# SCH_Dise_o2_2023-11-16.net
KiCad netlist of a schematic drawn in EasyEDA
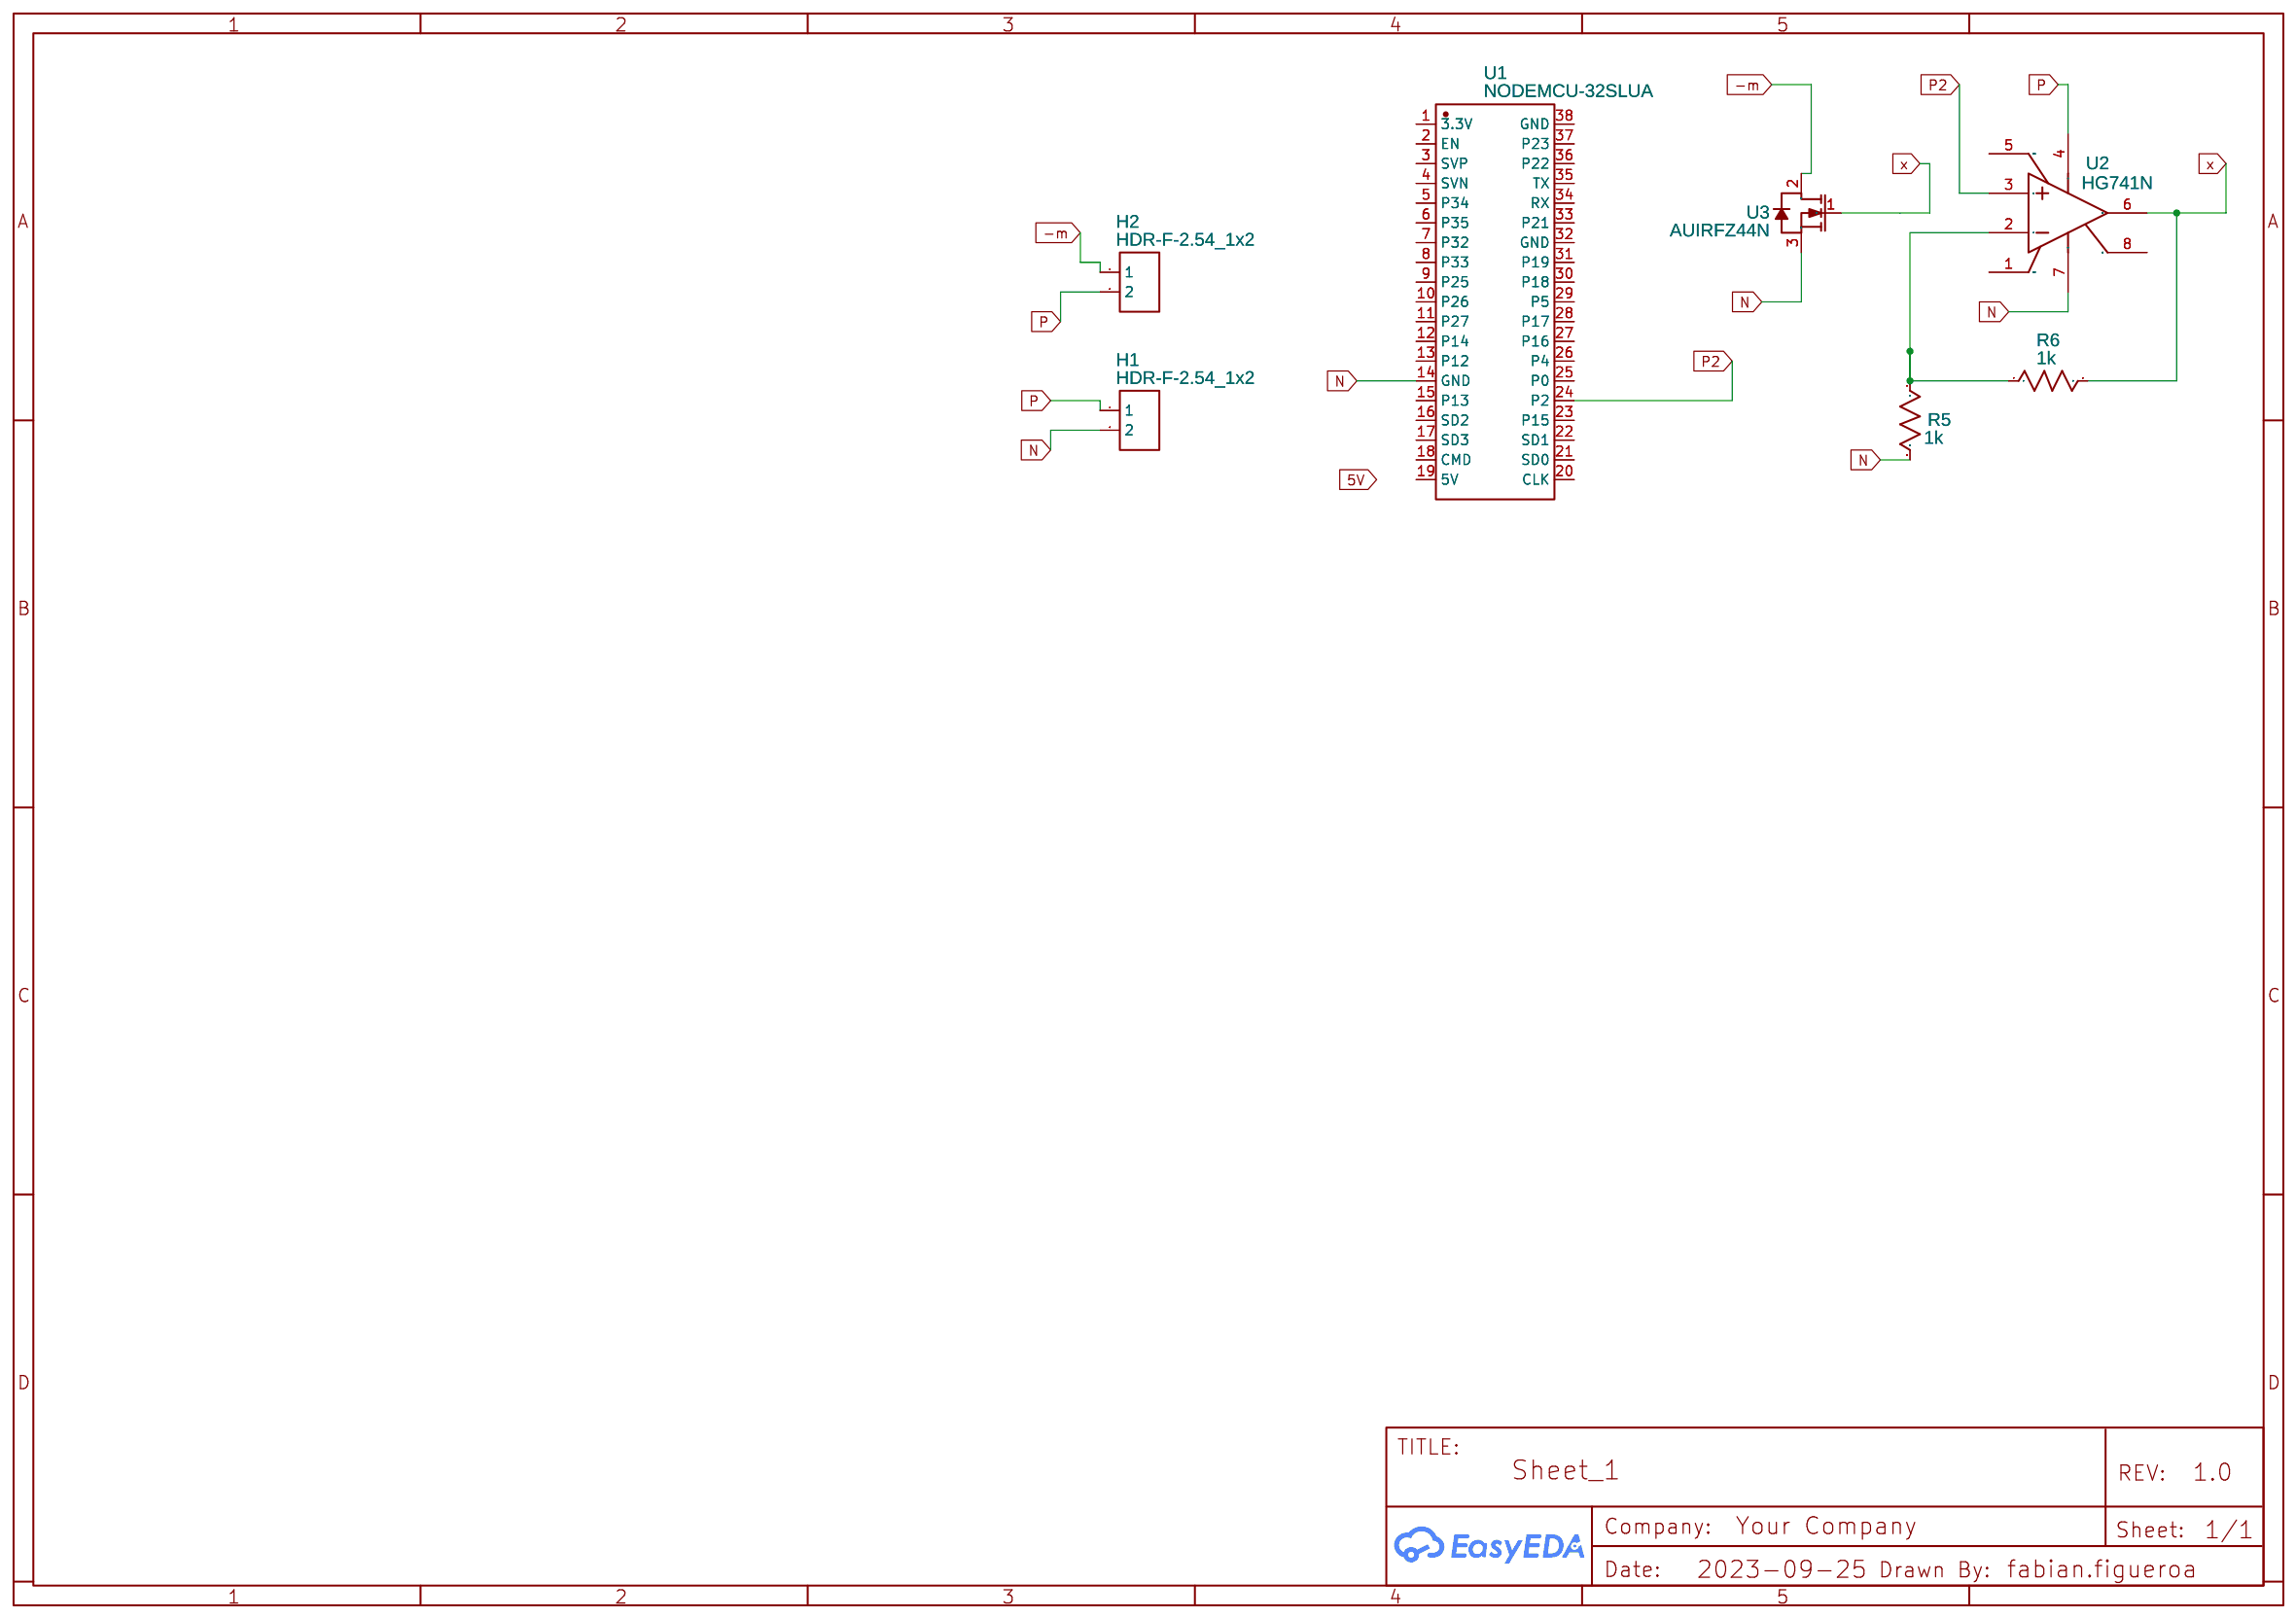
[diagram p0: schematic sheet]

(export (version "E")
  (design (tool "Eeschema 10.0.6"))
  (components
    (comp (ref "H1") (value "HDR-F-2.54_1x2") (libsource (lib "") (part "HDR-F-2.54_1x2")))
    (comp (ref "H2") (value "HDR-F-2.54_1x2") (libsource (lib "") (part "HDR-F-2.54_1x2")))
    (comp (ref "R5") (value "1k") (libsource (lib "") (part "R_AXIAL-0.4_US")))
    (comp (ref "R6") (value "1k") (libsource (lib "") (part "R_AXIAL-0.4_US_1")))
    (comp (ref "U1")
      (value "NODEMCU-32SLUA")
      (fields
        (field (name "Manufacturer Part") "NodeMCU-32SLua")
        (field (name "Manufacturer") "Ai-Thinker(安信可)")
      )
      (libsource (lib "") (part "NODEMCU-32SLUA"))
    )
    (comp (ref "U2")
      (value "HG741N")
      (fields (field (name "Manufacturer") "HGSEMI(华冠)"))
      (libsource (lib "") (part "HG741N"))
    )
    (comp (ref "U3")
      (value "AUIRFZ44N")
      (fields (field (name "Manufacturer") "Infineon(英飞凌)"))
      (libsource (lib "") (part "AUIRFZ44N"))
    )
  )
  (nets
    (net (code "1") (name "-m") (class "Default")
      (node (ref "H2") (pin "1") (pinfunction "1_1") (pintype "input"))
      (node (ref "U3") (pin "2") (pinfunction "D_2") (pintype "unspecified"))
    )
    (net (code "3") (name "N") (class "Default")
      (node (ref "H1") (pin "2") (pinfunction "2_2") (pintype "input"))
      (node (ref "R5") (pin "2") (pinfunction "2_2") (pintype "unspecified"))
      (node (ref "U1") (pin "14") (pinfunction "GND_14") (pintype "unspecified"))
      (node (ref "U2") (pin "7") (pinfunction "V+_7") (pintype "passive"))
      (node (ref "U3") (pin "3") (pinfunction "S_3") (pintype "unspecified"))
    )
    (net (code "4") (name "Net-(U2--IN)") (class "Default")
      (node (ref "R5") (pin "1") (pinfunction "1_1") (pintype "unspecified"))
      (node (ref "R6") (pin "1") (pinfunction "1_1") (pintype "unspecified"))
      (node (ref "U2") (pin "2") (pinfunction "-IN_2") (pintype "unspecified"))
    )
    (net (code "5") (name "P") (class "Default")
      (node (ref "H1") (pin "1") (pinfunction "1_1") (pintype "input"))
      (node (ref "H2") (pin "2") (pinfunction "2_2") (pintype "input"))
      (node (ref "U2") (pin "4") (pinfunction "V-_4") (pintype "passive"))
    )
    (net (code "6") (name "P2") (class "Default")
      (node (ref "U1") (pin "24") (pinfunction "P2_24") (pintype "unspecified"))
      (node (ref "U2") (pin "3") (pinfunction "+IN_3") (pintype "unspecified"))
    )
    (net (code "7") (name "unconnected-(U1-3.3V-Pad1)") (class "Default")
      (node (ref "U1") (pin "1") (pinfunction "3.3V_1") (pintype "unspecified"))
    )
    (net (code "8") (name "unconnected-(U1-5V-Pad19)") (class "Default")
      (node (ref "U1") (pin "19") (pinfunction "5V_19") (pintype "unspecified"))
    )
    (net (code "9") (name "unconnected-(U1-CLK-Pad20)") (class "Default")
      (node (ref "U1") (pin "20") (pinfunction "CLK_20") (pintype "unspecified"))
    )
    (net (code "10") (name "unconnected-(U1-CMD-Pad18)") (class "Default")
      (node (ref "U1") (pin "18") (pinfunction "CMD_18") (pintype "unspecified"))
    )
    (net (code "11") (name "unconnected-(U1-EN-Pad2)") (class "Default")
      (node (ref "U1") (pin "2") (pinfunction "EN_2") (pintype "unspecified"))
    )
    (net (code "12") (name "unconnected-(U1-GND-Pad32)") (class "Default")
      (node (ref "U1") (pin "32") (pinfunction "GND_32") (pintype "unspecified"))
    )
    (net (code "13") (name "unconnected-(U1-GND-Pad38)") (class "Default")
      (node (ref "U1") (pin "38") (pinfunction "GND_38") (pintype "unspecified"))
    )
    (net (code "14") (name "unconnected-(U1-P0-Pad25)") (class "Default")
      (node (ref "U1") (pin "25") (pinfunction "P0_25") (pintype "unspecified"))
    )
    (net (code "15") (name "unconnected-(U1-P4-Pad26)") (class "Default")
      (node (ref "U1") (pin "26") (pinfunction "P4_26") (pintype "unspecified"))
    )
    (net (code "16") (name "unconnected-(U1-P5-Pad29)") (class "Default")
      (node (ref "U1") (pin "29") (pinfunction "P5_29") (pintype "unspecified"))
    )
    (net (code "17") (name "unconnected-(U1-P12-Pad13)") (class "Default")
      (node (ref "U1") (pin "13") (pinfunction "P12_13") (pintype "unspecified"))
    )
    (net (code "18") (name "unconnected-(U1-P13-Pad15)") (class "Default")
      (node (ref "U1") (pin "15") (pinfunction "P13_15") (pintype "unspecified"))
    )
    (net (code "19") (name "unconnected-(U1-P14-Pad12)") (class "Default")
      (node (ref "U1") (pin "12") (pinfunction "P14_12") (pintype "unspecified"))
    )
    (net (code "20") (name "unconnected-(U1-P15-Pad23)") (class "Default")
      (node (ref "U1") (pin "23") (pinfunction "P15_23") (pintype "unspecified"))
    )
    (net (code "21") (name "unconnected-(U1-P16-Pad27)") (class "Default")
      (node (ref "U1") (pin "27") (pinfunction "P16_27") (pintype "unspecified"))
    )
    (net (code "22") (name "unconnected-(U1-P17-Pad28)") (class "Default")
      (node (ref "U1") (pin "28") (pinfunction "P17_28") (pintype "unspecified"))
    )
    (net (code "23") (name "unconnected-(U1-P18-Pad30)") (class "Default")
      (node (ref "U1") (pin "30") (pinfunction "P18_30") (pintype "unspecified"))
    )
    (net (code "24") (name "unconnected-(U1-P19-Pad31)") (class "Default")
      (node (ref "U1") (pin "31") (pinfunction "P19_31") (pintype "unspecified"))
    )
    (net (code "25") (name "unconnected-(U1-P21-Pad33)") (class "Default")
      (node (ref "U1") (pin "33") (pinfunction "P21_33") (pintype "unspecified"))
    )
    (net (code "26") (name "unconnected-(U1-P22-Pad36)") (class "Default")
      (node (ref "U1") (pin "36") (pinfunction "P22_36") (pintype "unspecified"))
    )
    (net (code "27") (name "unconnected-(U1-P23-Pad37)") (class "Default")
      (node (ref "U1") (pin "37") (pinfunction "P23_37") (pintype "unspecified"))
    )
    (net (code "28") (name "unconnected-(U1-P25-Pad9)") (class "Default")
      (node (ref "U1") (pin "9") (pinfunction "P25_9") (pintype "unspecified"))
    )
    (net (code "29") (name "unconnected-(U1-P26-Pad10)") (class "Default")
      (node (ref "U1") (pin "10") (pinfunction "P26_10") (pintype "unspecified"))
    )
    (net (code "30") (name "unconnected-(U1-P27-Pad11)") (class "Default")
      (node (ref "U1") (pin "11") (pinfunction "P27_11") (pintype "unspecified"))
    )
    (net (code "31") (name "unconnected-(U1-P32-Pad7)") (class "Default")
      (node (ref "U1") (pin "7") (pinfunction "P32_7") (pintype "unspecified"))
    )
    (net (code "32") (name "unconnected-(U1-P33-Pad8)") (class "Default")
      (node (ref "U1") (pin "8") (pinfunction "P33_8") (pintype "unspecified"))
    )
    (net (code "33") (name "unconnected-(U1-P34-Pad5)") (class "Default")
      (node (ref "U1") (pin "5") (pinfunction "P34_5") (pintype "unspecified"))
    )
    (net (code "34") (name "unconnected-(U1-P35-Pad6)") (class "Default")
      (node (ref "U1") (pin "6") (pinfunction "P35_6") (pintype "unspecified"))
    )
    (net (code "35") (name "unconnected-(U1-RX-Pad34)") (class "Default")
      (node (ref "U1") (pin "34") (pinfunction "RX_34") (pintype "unspecified"))
    )
    (net (code "36") (name "unconnected-(U1-SD0-Pad21)") (class "Default")
      (node (ref "U1") (pin "21") (pinfunction "SD0_21") (pintype "unspecified"))
    )
    (net (code "37") (name "unconnected-(U1-SD1-Pad22)") (class "Default")
      (node (ref "U1") (pin "22") (pinfunction "SD1_22") (pintype "unspecified"))
    )
    (net (code "38") (name "unconnected-(U1-SD2-Pad16)") (class "Default")
      (node (ref "U1") (pin "16") (pinfunction "SD2_16") (pintype "unspecified"))
    )
    (net (code "39") (name "unconnected-(U1-SD3-Pad17)") (class "Default")
      (node (ref "U1") (pin "17") (pinfunction "SD3_17") (pintype "unspecified"))
    )
    (net (code "40") (name "unconnected-(U1-SVN-Pad4)") (class "Default")
      (node (ref "U1") (pin "4") (pinfunction "SVN_4") (pintype "unspecified"))
    )
    (net (code "41") (name "unconnected-(U1-SVP-Pad3)") (class "Default")
      (node (ref "U1") (pin "3") (pinfunction "SVP_3") (pintype "unspecified"))
    )
    (net (code "42") (name "unconnected-(U1-TX-Pad35)") (class "Default")
      (node (ref "U1") (pin "35") (pinfunction "TX_35") (pintype "unspecified"))
    )
    (net (code "43") (name "unconnected-(U2-NC-Pad8)") (class "Default")
      (node (ref "U2") (pin "8") (pinfunction "NC_8") (pintype "unspecified"))
    )
    (net (code "44") (name "unconnected-(U2-OFFSET_NULL-Pad1)") (class "Default")
      (node (ref "U2") (pin "1") (pinfunction "OFFSET_NULL_1") (pintype "unspecified"))
    )
    (net (code "45") (name "unconnected-(U2-OFFSET_NULL-Pad5)") (class "Default")
      (node (ref "U2") (pin "5") (pinfunction "OFFSET_NULL_5") (pintype "unspecified"))
    )
    (net (code "46") (name "x") (class "Default")
      (node (ref "R6") (pin "2") (pinfunction "2_2") (pintype "unspecified"))
      (node (ref "U2") (pin "6") (pinfunction "VOUT_6") (pintype "unspecified"))
      (node (ref "U3") (pin "1") (pinfunction "G_1") (pintype "unspecified"))
    )
  )
)
